# oLoRa-part-SD.net
KiCad netlist of a schematic drawn in EasyEDA
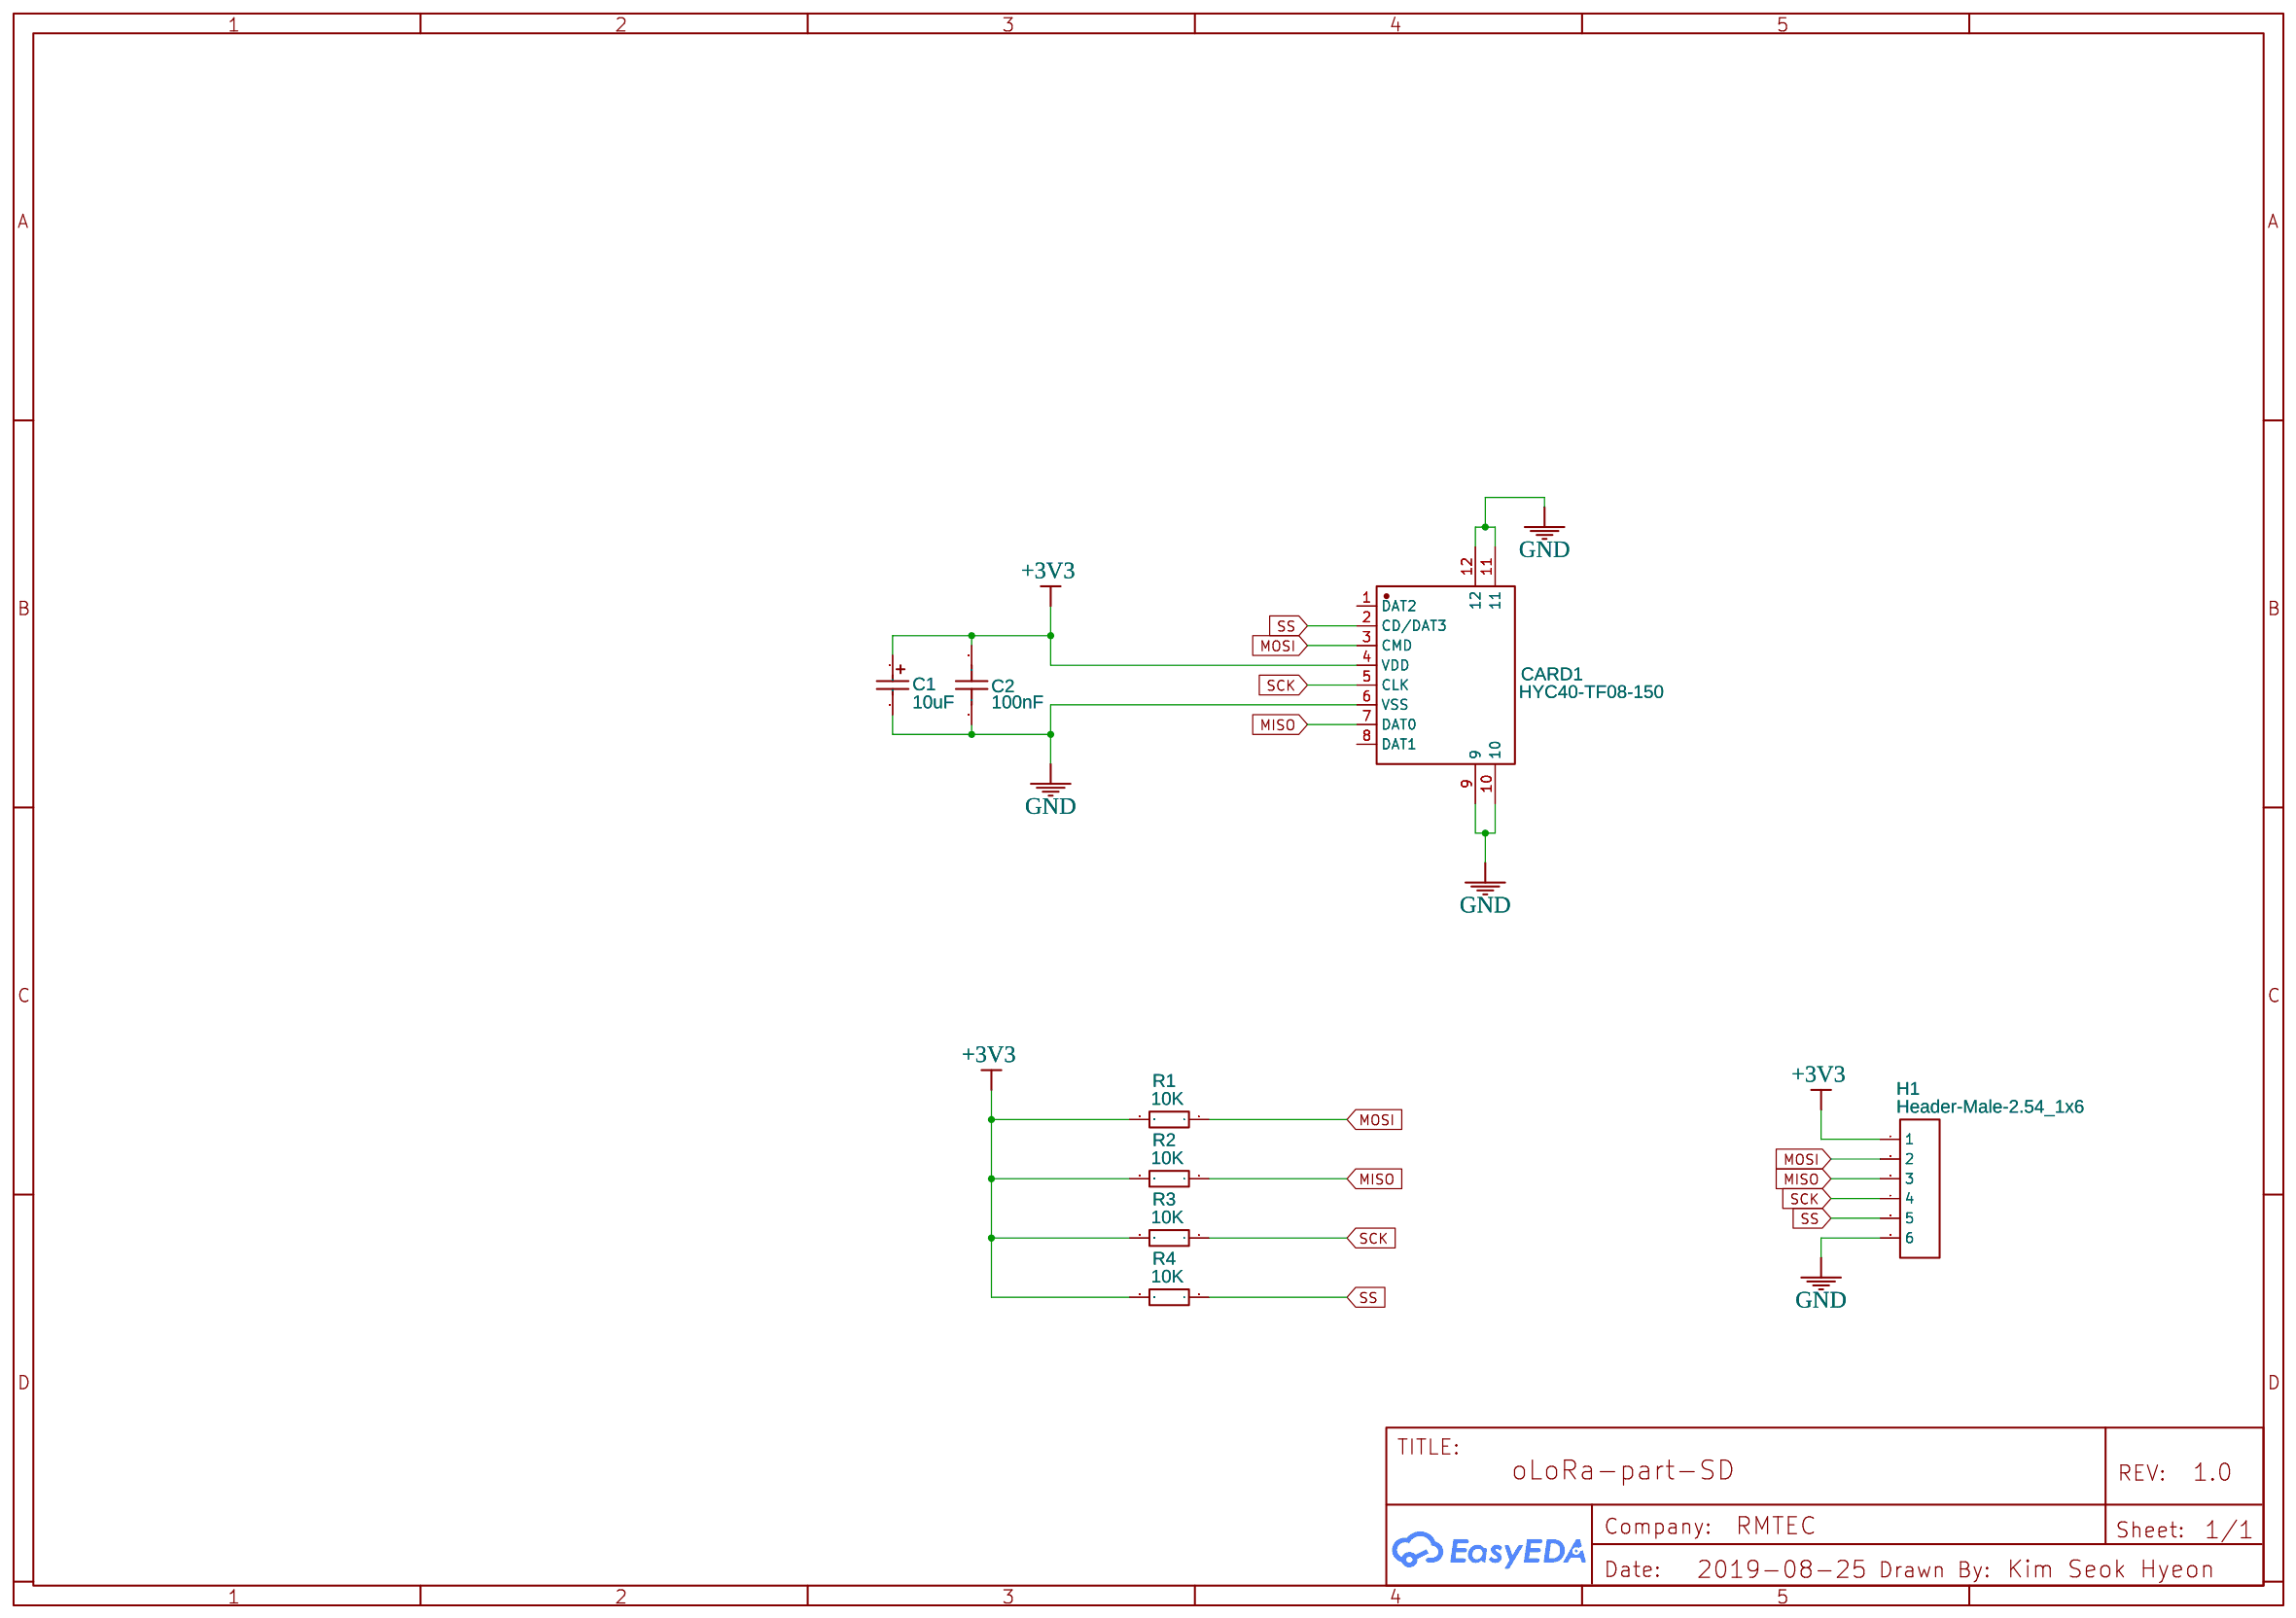
[diagram p0: schematic sheet]

(export (version "E")
  (design (tool "Eeschema 10.0.6"))
  (components
    (comp (ref "C1")
      (value "10uF")
      (fields
        (field (name "BOM_Manufacturer Part") "TAJA106K016RNJ")
        (field (name "BOM_Supplier Part") "C7171")
      )
      (libsource (lib "") (part "TAJA106K016RNJ"))
    )
    (comp (ref "C2")
      (value "100nF")
      (fields
        (field (name "BOM_Manufacturer Part") "CC0603KRX7R9BB104")
        (field (name "BOM_Supplier Part") "C14663")
      )
      (libsource (lib "") (part "CC0603KRX7R9BB104"))
    )
    (comp (ref "CARD1")
      (value "HYC40-TF08-150")
      (fields (field (name "BOM_Supplier Part") "C341096"))
      (libsource (lib "") (part "Unknown_720_330"))
    )
    (comp (ref "H1")
      (value "Header-Male-2.54_1x6")
      (fields (field (name "BOM_Supplier Part") "C37208"))
      (libsource (lib "") (part "Unknown_960_595"))
    )
    (comp (ref "R1")
      (value "10K")
      (fields
        (field (name "BOM_Manufacturer Part") "0603WAF1002T5E")
        (field (name "BOM_Supplier Part") "C25804")
      )
      (libsource (lib "") (part "0603WAF1002T5E"))
    )
    (comp (ref "R2")
      (value "10K")
      (fields
        (field (name "BOM_Manufacturer Part") "0603WAF1002T5E")
        (field (name "BOM_Supplier Part") "C25804")
      )
      (libsource (lib "") (part "0603WAF1002T5E"))
    )
    (comp (ref "R3")
      (value "10K")
      (fields
        (field (name "BOM_Manufacturer Part") "0603WAF1002T5E")
        (field (name "BOM_Supplier Part") "C25804")
      )
      (libsource (lib "") (part "0603WAF1002T5E"))
    )
    (comp (ref "R4")
      (value "10K")
      (fields
        (field (name "BOM_Manufacturer Part") "0603WAF1002T5E")
        (field (name "BOM_Supplier Part") "C25804")
      )
      (libsource (lib "") (part "0603WAF1002T5E"))
    )
  )
  (nets
    (net (code "1") (name "+3V3") (class "Default")
      (node (ref "C1") (pin "1") (pinfunction "1_1") (pintype "input"))
      (node (ref "C2") (pin "2") (pinfunction "2_2") (pintype "unspecified"))
      (node (ref "CARD1") (pin "4") (pinfunction "VDD_4") (pintype "unspecified"))
      (node (ref "H1") (pin "1") (pinfunction "1_1") (pintype "input"))
      (node (ref "R1") (pin "2") (pinfunction "2_2") (pintype "input"))
      (node (ref "R2") (pin "2") (pinfunction "2_2") (pintype "input"))
      (node (ref "R3") (pin "2") (pinfunction "2_2") (pintype "input"))
      (node (ref "R4") (pin "2") (pinfunction "2_2") (pintype "input"))
    )
    (net (code "2") (name "GND") (class "Default")
      (node (ref "C1") (pin "2") (pinfunction "2_2") (pintype "input"))
      (node (ref "C2") (pin "1") (pinfunction "1_1") (pintype "unspecified"))
      (node (ref "CARD1") (pin "10") (pinfunction "10_10") (pintype "unspecified"))
      (node (ref "CARD1") (pin "11") (pinfunction "11_11") (pintype "unspecified"))
      (node (ref "CARD1") (pin "12") (pinfunction "12_12") (pintype "unspecified"))
      (node (ref "CARD1") (pin "6") (pinfunction "VSS_6") (pintype "unspecified"))
      (node (ref "CARD1") (pin "9") (pinfunction "9_9") (pintype "unspecified"))
      (node (ref "H1") (pin "6") (pinfunction "6_6") (pintype "input"))
    )
    (net (code "3") (name "MISO") (class "Default")
      (node (ref "CARD1") (pin "7") (pinfunction "DAT0_7") (pintype "unspecified"))
      (node (ref "H1") (pin "3") (pinfunction "3_3") (pintype "input"))
      (node (ref "R2") (pin "1") (pinfunction "1_1") (pintype "input"))
    )
    (net (code "4") (name "MOSI") (class "Default")
      (node (ref "CARD1") (pin "3") (pinfunction "CMD_3") (pintype "unspecified"))
      (node (ref "H1") (pin "2") (pinfunction "2_2") (pintype "input"))
      (node (ref "R1") (pin "1") (pinfunction "1_1") (pintype "input"))
    )
    (net (code "5") (name "SCK") (class "Default")
      (node (ref "CARD1") (pin "5") (pinfunction "CLK_5") (pintype "unspecified"))
      (node (ref "H1") (pin "4") (pinfunction "4_4") (pintype "input"))
      (node (ref "R3") (pin "1") (pinfunction "1_1") (pintype "input"))
    )
    (net (code "6") (name "SS") (class "Default")
      (node (ref "CARD1") (pin "2") (pinfunction "CD/DAT3_2") (pintype "unspecified"))
      (node (ref "H1") (pin "5") (pinfunction "5_5") (pintype "input"))
      (node (ref "R4") (pin "1") (pinfunction "1_1") (pintype "input"))
    )
    (net (code "7") (name "unconnected-(CARD1-DAT1-Pad8)") (class "Default")
      (node (ref "CARD1") (pin "8") (pinfunction "DAT1_8") (pintype "unspecified"))
    )
    (net (code "8") (name "unconnected-(CARD1-DAT2-Pad1)") (class "Default")
      (node (ref "CARD1") (pin "1") (pinfunction "DAT2_1") (pintype "unspecified"))
    )
  )
)
